# board_pa94.net
KiCad netlist of a schematic drawn in Altium Designer
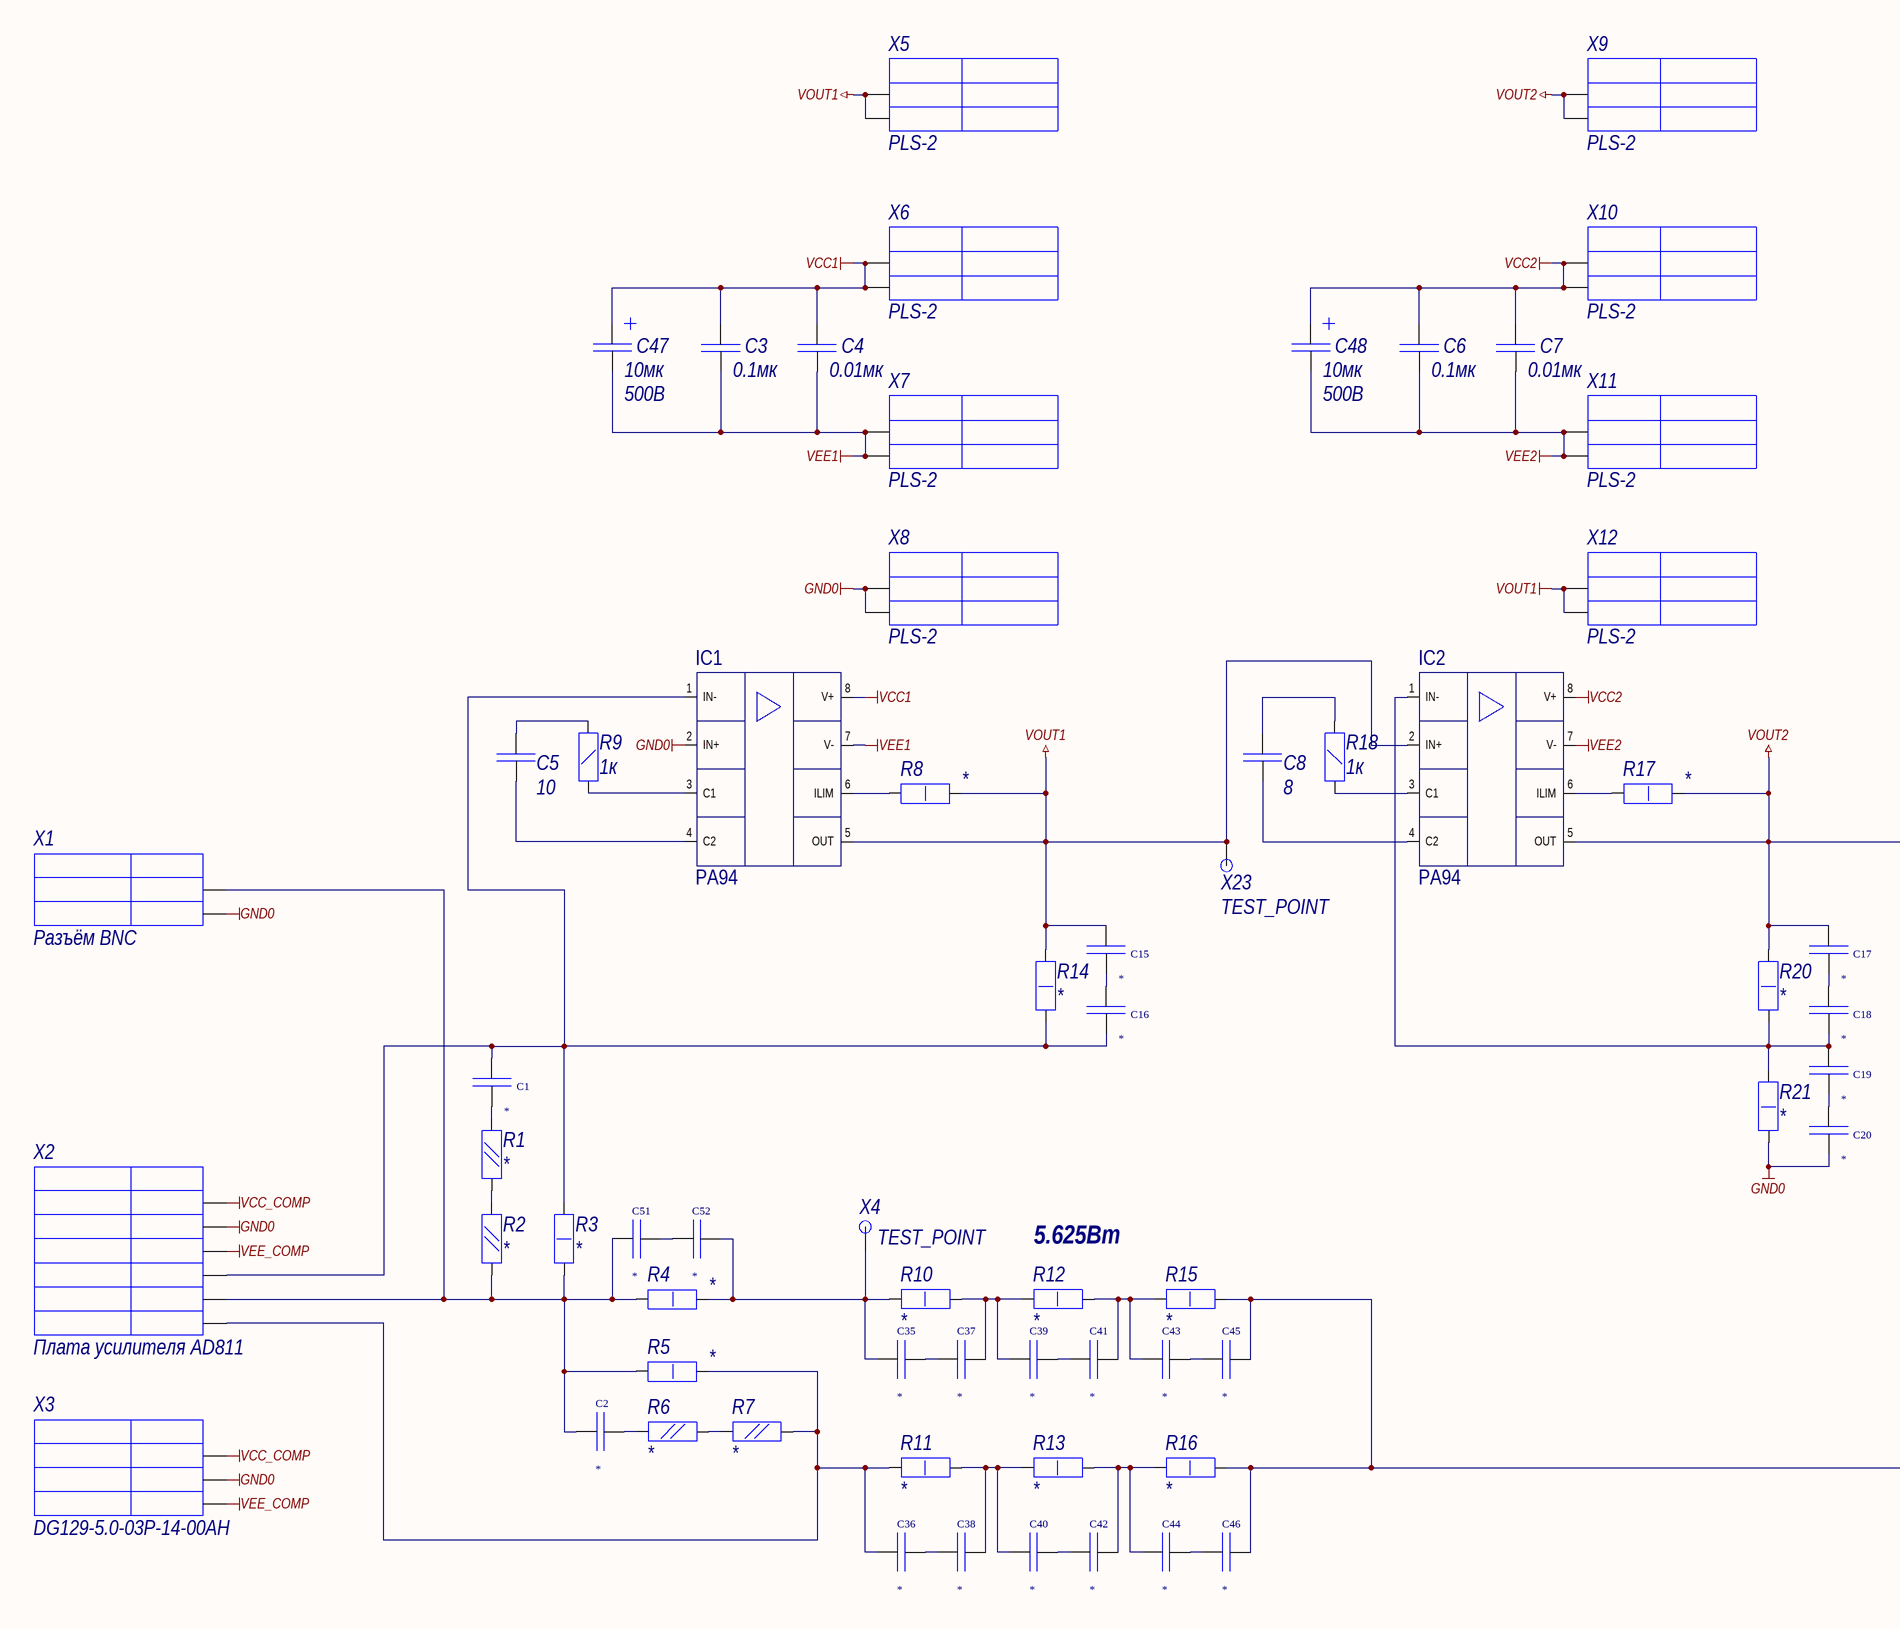
[diagram p0: board_pa94 (2).SchDoc, left]
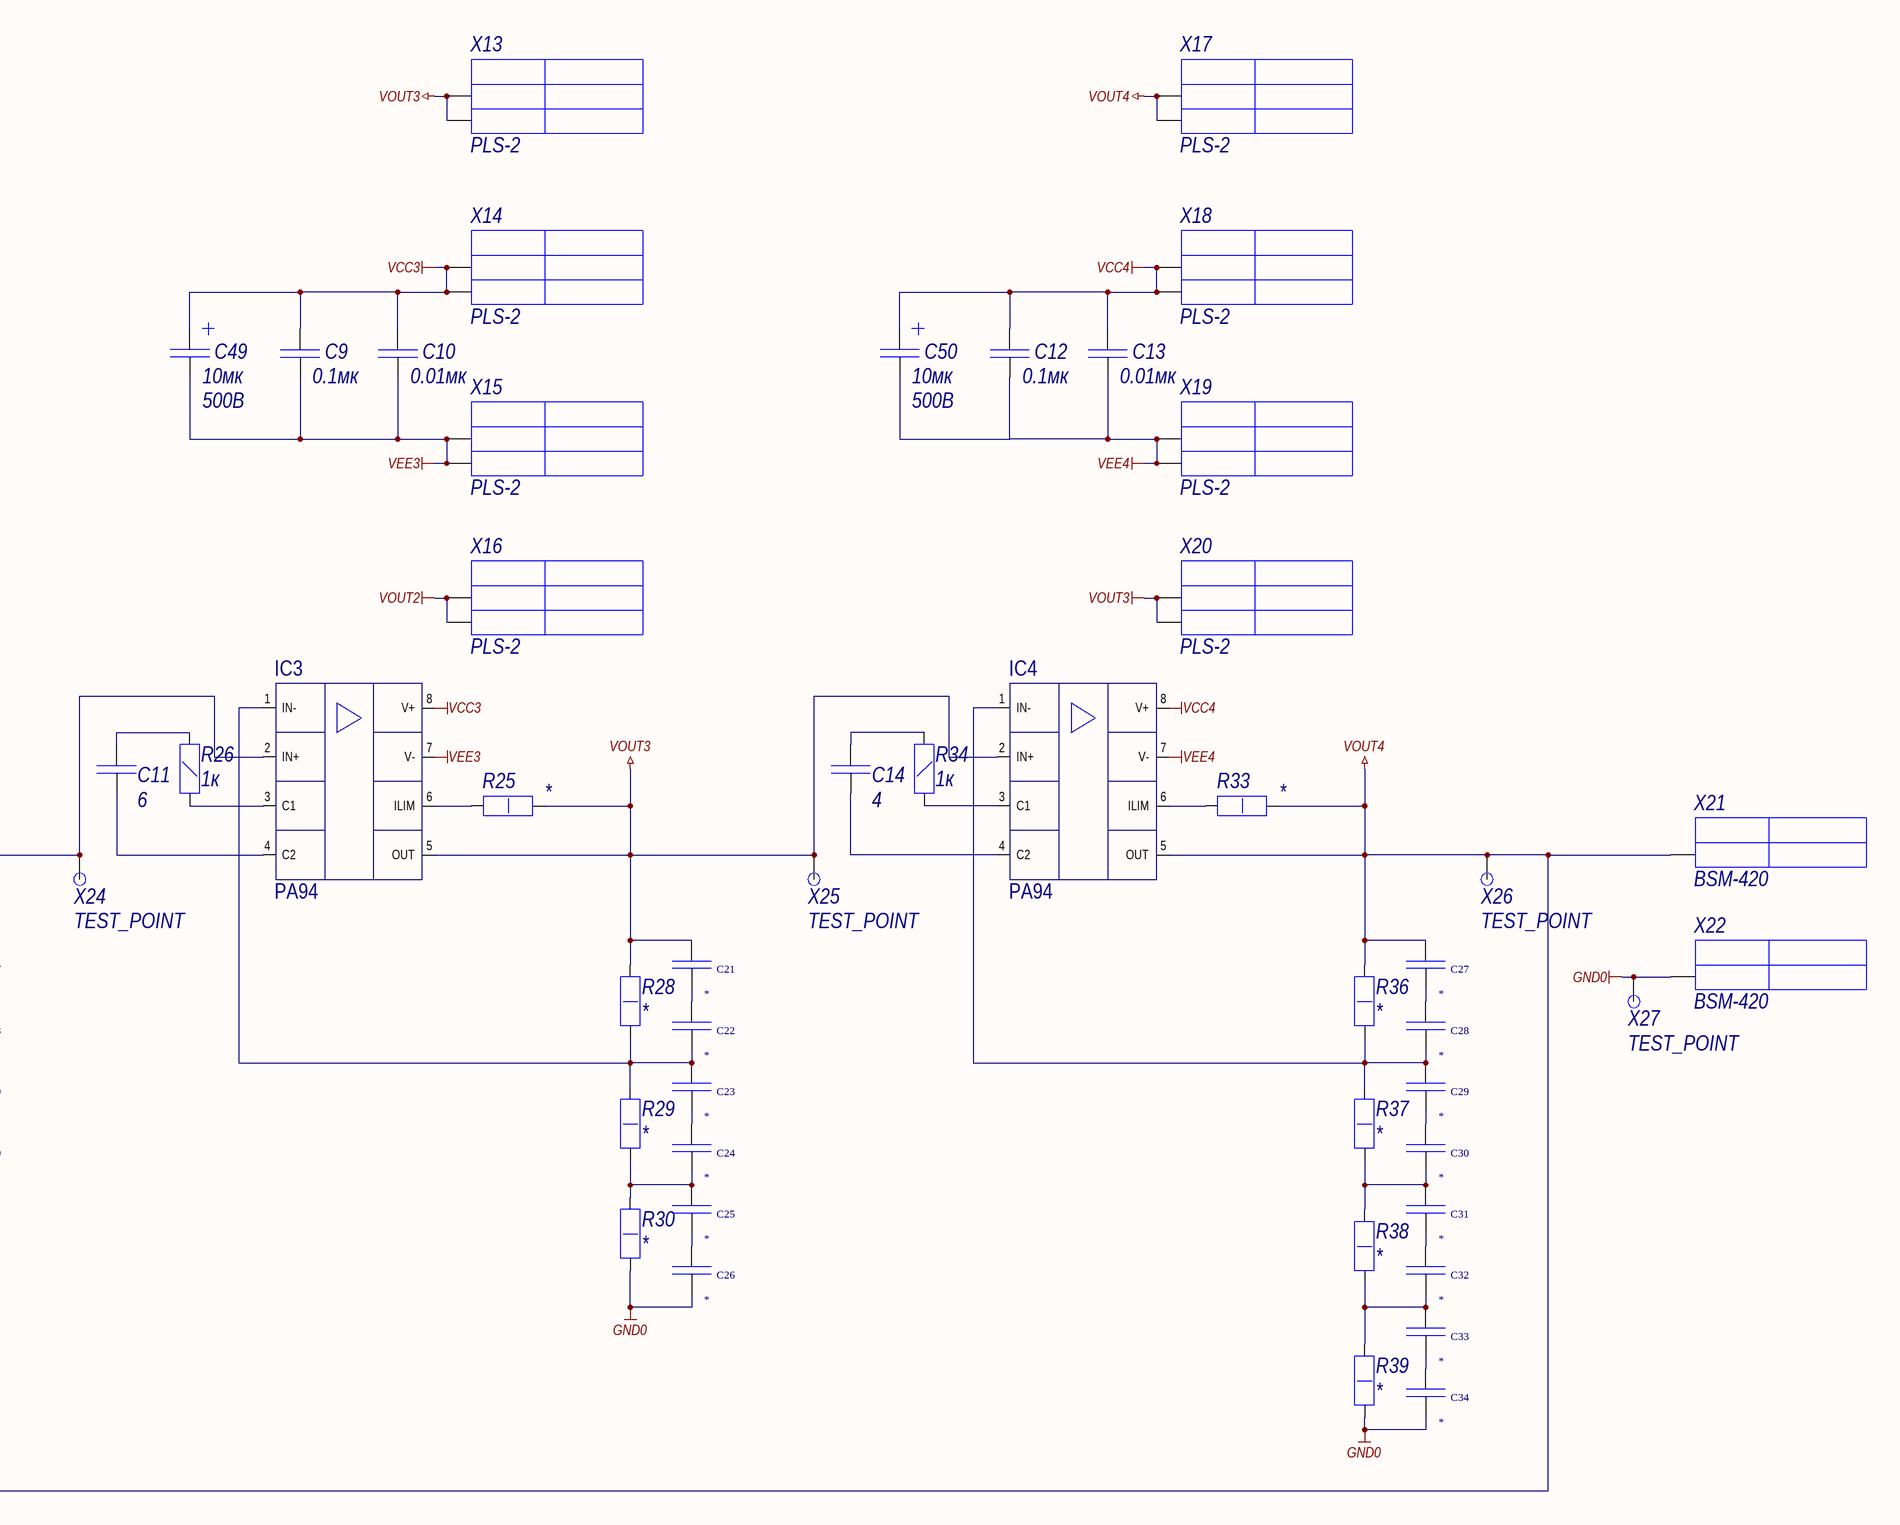
[diagram p1: board_pa94 (2).SchDoc, right]

(export (version "E")
  (design (tool "Eeschema 10.0.6"))
  (components
    (comp (ref "C1") (value "*") (footprint "C-0805") (libsource (lib "Capacitor") (part "C0805")))
    (comp (ref "C2") (value "*") (footprint "C-0805") (libsource (lib "Capacitor") (part "C0805")))
    (comp (ref "C3")
      (value "0.1мк")
      (footprint "C-1812")
      (fields (field (name "VOLTAGE") "630"))
      (libsource (lib "Capacitor") (part "C1812"))
    )
    (comp (ref "C4")
      (value "0.01мк")
      (footprint "C-1206")
      (fields (field (name "VOLTAGE") "630"))
      (libsource (lib "Capacitor") (part "C1206"))
    )
    (comp (ref "C5")
      (value "10")
      (footprint "C-1206")
      (fields (field (name "VOLTAGE") "630В"))
      (libsource (lib "Capacitor") (part "C1206"))
    )
    (comp (ref "C6")
      (value "0.1мк")
      (footprint "C-1812")
      (fields (field (name "VOLTAGE") "630"))
      (libsource (lib "Capacitor") (part "C1812"))
    )
    (comp (ref "C7")
      (value "0.01мк")
      (footprint "C-1206")
      (fields (field (name "VOLTAGE") "630"))
      (libsource (lib "Capacitor") (part "C1206"))
    )
    (comp (ref "C8")
      (value "8")
      (footprint "C-1206")
      (fields (field (name "VOLTAGE") "630В"))
      (libsource (lib "Capacitor") (part "C1206"))
    )
    (comp (ref "C9")
      (value "0.1мк")
      (footprint "C-1812")
      (fields (field (name "VOLTAGE") "630"))
      (libsource (lib "Capacitor") (part "C1812"))
    )
    (comp (ref "C10")
      (value "0.01мк")
      (footprint "C-1206")
      (fields (field (name "VOLTAGE") "630"))
      (libsource (lib "Capacitor") (part "C1206"))
    )
    (comp (ref "C11")
      (value "6")
      (footprint "C-1206")
      (fields (field (name "VOLTAGE") "630В"))
      (libsource (lib "Capacitor") (part "C1206"))
    )
    (comp (ref "C12")
      (value "0.1мк")
      (footprint "C-1812")
      (fields (field (name "VOLTAGE") "630"))
      (libsource (lib "Capacitor") (part "C1812"))
    )
    (comp (ref "C13")
      (value "0.01мк")
      (footprint "C-1206")
      (fields (field (name "VOLTAGE") "630"))
      (libsource (lib "Capacitor") (part "C1206"))
    )
    (comp (ref "C14")
      (value "4")
      (footprint "C-1206")
      (fields (field (name "VOLTAGE") "630В"))
      (libsource (lib "Capacitor") (part "C1206"))
    )
    (comp (ref "C15") (value "*") (footprint "C-0805") (libsource (lib "Capacitor") (part "C0805")))
    (comp (ref "C16") (value "*") (footprint "C-0805") (libsource (lib "Capacitor") (part "C0805")))
    (comp (ref "C17") (value "*") (footprint "C-0805") (libsource (lib "Capacitor") (part "C0805")))
    (comp (ref "C18") (value "*") (footprint "C-0805") (libsource (lib "Capacitor") (part "C0805")))
    (comp (ref "C19") (value "*") (footprint "C-0805") (libsource (lib "Capacitor") (part "C0805")))
    (comp (ref "C20") (value "*") (footprint "C-0805") (libsource (lib "Capacitor") (part "C0805")))
    (comp (ref "C21") (value "*") (footprint "C-0805") (libsource (lib "Capacitor") (part "C0805")))
    (comp (ref "C22") (value "*") (footprint "C-0805") (libsource (lib "Capacitor") (part "C0805")))
    (comp (ref "C23") (value "*") (footprint "C-0805") (libsource (lib "Capacitor") (part "C0805")))
    (comp (ref "C24") (value "*") (footprint "C-0805") (libsource (lib "Capacitor") (part "C0805")))
    (comp (ref "C25") (value "*") (footprint "C-0805") (libsource (lib "Capacitor") (part "C0805")))
    (comp (ref "C26") (value "*") (footprint "C-0805") (libsource (lib "Capacitor") (part "C0805")))
    (comp (ref "C27") (value "*") (footprint "C-0805") (libsource (lib "Capacitor") (part "C0805")))
    (comp (ref "C28") (value "*") (footprint "C-0805") (libsource (lib "Capacitor") (part "C0805")))
    (comp (ref "C29") (value "*") (footprint "C-0805") (libsource (lib "Capacitor") (part "C0805")))
    (comp (ref "C30") (value "*") (footprint "C-0805") (libsource (lib "Capacitor") (part "C0805")))
    (comp (ref "C31") (value "*") (footprint "C-0805") (libsource (lib "Capacitor") (part "C0805")))
    (comp (ref "C32") (value "*") (footprint "C-0805") (libsource (lib "Capacitor") (part "C0805")))
    (comp (ref "C33") (value "*") (footprint "C-0805") (libsource (lib "Capacitor") (part "C0805")))
    (comp (ref "C34") (value "*") (footprint "C-0805") (libsource (lib "Capacitor") (part "C0805")))
    (comp (ref "C35") (value "*") (footprint "C-0805") (libsource (lib "Capacitor") (part "C0805")))
    (comp (ref "C36") (value "*") (footprint "C-0805") (libsource (lib "Capacitor") (part "C0805")))
    (comp (ref "C37") (value "*") (footprint "C-0805") (libsource (lib "Capacitor") (part "C0805")))
    (comp (ref "C38") (value "*") (footprint "C-0805") (libsource (lib "Capacitor") (part "C0805")))
    (comp (ref "C39") (value "*") (footprint "C-0805") (libsource (lib "Capacitor") (part "C0805")))
    (comp (ref "C40") (value "*") (footprint "C-0805") (libsource (lib "Capacitor") (part "C0805")))
    (comp (ref "C41") (value "*") (footprint "C-0805") (libsource (lib "Capacitor") (part "C0805")))
    (comp (ref "C42") (value "*") (footprint "C-0805") (libsource (lib "Capacitor") (part "C0805")))
    (comp (ref "C43") (value "*") (footprint "C-0805") (libsource (lib "Capacitor") (part "C0805")))
    (comp (ref "C44") (value "*") (footprint "C-0805") (libsource (lib "Capacitor") (part "C0805")))
    (comp (ref "C45") (value "*") (footprint "C-0805") (libsource (lib "Capacitor") (part "C0805")))
    (comp (ref "C46") (value "*") (footprint "C-0805") (libsource (lib "Capacitor") (part "C0805")))
    (comp (ref "C47")
      (value "10мк")
      (footprint "CAP: D10C5H12.5")
      (description "Конденсатор электролитический")
      (fields (field (name "VOLTAGE") "500В"))
      (libsource (lib "Capacitor") (part "Aluminum electrolytic capacitor"))
    )
    (comp (ref "C48")
      (value "10мк")
      (footprint "CAP: D10C5H12.5")
      (description "Конденсатор электролитический")
      (fields (field (name "VOLTAGE") "500В"))
      (libsource (lib "Capacitor") (part "Aluminum electrolytic capacitor"))
    )
    (comp (ref "C49")
      (value "10мк")
      (footprint "CAP: D10C5H12.5")
      (description "Конденсатор электролитический")
      (fields (field (name "VOLTAGE") "500В"))
      (libsource (lib "Capacitor") (part "Aluminum electrolytic capacitor"))
    )
    (comp (ref "C50")
      (value "10мк")
      (footprint "CAP: D10C5H12.5")
      (description "Конденсатор электролитический")
      (fields (field (name "VOLTAGE") "500В"))
      (libsource (lib "Capacitor") (part "Aluminum electrolytic capacitor"))
    )
    (comp (ref "C51") (value "*") (footprint "C-0805") (libsource (lib "Capacitor") (part "C0805")))
    (comp (ref "C52") (value "*") (footprint "C-0805") (libsource (lib "Capacitor") (part "C0805")))
    (comp (ref "IC1")
      (value "PA94")
      (footprint "PCBComponent_1")
      (description "Power Amplifier 1 Circuit 8-SIP")
      (fields (field (name "MF") "Apex Microtechnology") (field (name "DIGI-KEY_PART_NUMBER") "598-1334-ND"))
      (libsource (lib "PA94") (part "PA94"))
    )
    (comp (ref "IC2")
      (value "PA94")
      (footprint "PCBComponent_1")
      (description "Power Amplifier 1 Circuit 8-SIP")
      (fields (field (name "MF") "Apex Microtechnology") (field (name "DIGI-KEY_PART_NUMBER") "598-1334-ND"))
      (libsource (lib "PA94") (part "PA94"))
    )
    (comp (ref "IC3")
      (value "PA94")
      (footprint "PCBComponent_1")
      (description "Power Amplifier 1 Circuit 8-SIP")
      (fields (field (name "MF") "Apex Microtechnology") (field (name "DIGI-KEY_PART_NUMBER") "598-1334-ND"))
      (libsource (lib "PA94") (part "PA94"))
    )
    (comp (ref "IC4")
      (value "PA94")
      (footprint "PCBComponent_1")
      (description "Power Amplifier 1 Circuit 8-SIP")
      (fields (field (name "MF") "Apex Microtechnology") (field (name "DIGI-KEY_PART_NUMBER") "598-1334-ND"))
      (libsource (lib "PA94") (part "PA94"))
    )
    (comp (ref "R1")
      (value "*")
      (footprint "R-0805")
      (description "Резистор SMD")
      (fields (field (name "TOLERANCE") "5%"))
      (libsource (lib "Resistor") (part "R0805"))
    )
    (comp (ref "R2")
      (value "*")
      (footprint "R-0805")
      (description "Резистор SMD")
      (fields (field (name "TOLERANCE") "5%"))
      (libsource (lib "Resistor") (part "R0805"))
    )
    (comp (ref "R3")
      (value "*")
      (footprint "R-2512")
      (description "Резистор SMD")
      (fields (field (name "TOLERANCE") "5%"))
      (libsource (lib "Resistor") (part "R2512"))
    )
    (comp (ref "R4")
      (value "*")
      (footprint "R-2512")
      (description "Резистор SMD")
      (fields (field (name "TOLERANCE") "5%"))
      (libsource (lib "Resistor") (part "R2512"))
    )
    (comp (ref "R5")
      (value "*")
      (footprint "R-2512")
      (description "Резистор SMD")
      (fields (field (name "TOLERANCE") "5%"))
      (libsource (lib "Resistor") (part "R2512"))
    )
    (comp (ref "R6")
      (value "*")
      (footprint "R-0805")
      (description "Резистор SMD")
      (fields (field (name "TOLERANCE") "5%"))
      (libsource (lib "Resistor") (part "R0805"))
    )
    (comp (ref "R7")
      (value "*")
      (footprint "R-0805")
      (description "Резистор SMD")
      (fields (field (name "TOLERANCE") "5%"))
      (libsource (lib "Resistor") (part "R0805"))
    )
    (comp (ref "R8")
      (value "*")
      (footprint "R-2512")
      (description "Резистор SMD")
      (fields (field (name "TOLERANCE") "5%"))
      (libsource (lib "Resistor") (part "R2512"))
    )
    (comp (ref "R9")
      (value "1к")
      (footprint "R-1206")
      (description "Резистор SMD")
      (fields (field (name "TOLERANCE") "5%"))
      (libsource (lib "Resistor") (part "R1206"))
    )
    (comp (ref "R10")
      (value "*")
      (footprint "R-2512")
      (description "Резистор SMD")
      (fields (field (name "TOLERANCE") "5%"))
      (libsource (lib "Resistor") (part "R2512"))
    )
    (comp (ref "R11")
      (value "*")
      (footprint "R-2512")
      (description "Резистор SMD")
      (fields (field (name "TOLERANCE") "5%"))
      (libsource (lib "Resistor") (part "R2512"))
    )
    (comp (ref "R12")
      (value "*")
      (footprint "R-2512")
      (description "Резистор SMD")
      (fields (field (name "TOLERANCE") "5%"))
      (libsource (lib "Resistor") (part "R2512"))
    )
    (comp (ref "R13")
      (value "*")
      (footprint "R-2512")
      (description "Резистор SMD")
      (fields (field (name "TOLERANCE") "5%"))
      (libsource (lib "Resistor") (part "R2512"))
    )
    (comp (ref "R14")
      (value "*")
      (footprint "R-2512")
      (description "Резистор SMD")
      (fields (field (name "TOLERANCE") "5%"))
      (libsource (lib "Resistor") (part "R2512"))
    )
    (comp (ref "R15")
      (value "*")
      (footprint "R-2512")
      (description "Резистор SMD")
      (fields (field (name "TOLERANCE") "5%"))
      (libsource (lib "Resistor") (part "R2512"))
    )
    (comp (ref "R16")
      (value "*")
      (footprint "R-2512")
      (description "Резистор SMD")
      (fields (field (name "TOLERANCE") "5%"))
      (libsource (lib "Resistor") (part "R2512"))
    )
    (comp (ref "R17")
      (value "*")
      (footprint "R-2512")
      (description "Резистор SMD")
      (fields (field (name "TOLERANCE") "5%"))
      (libsource (lib "Resistor") (part "R2512"))
    )
    (comp (ref "R18")
      (value "1к")
      (footprint "R-1206")
      (description "Резистор SMD")
      (fields (field (name "TOLERANCE") "5%"))
      (libsource (lib "Resistor") (part "R1206"))
    )
    (comp (ref "R20")
      (value "*")
      (footprint "R-2512")
      (description "Резистор SMD")
      (fields (field (name "TOLERANCE") "5%"))
      (libsource (lib "Resistor") (part "R2512"))
    )
    (comp (ref "R21")
      (value "*")
      (footprint "R-2512")
      (description "Резистор SMD")
      (fields (field (name "TOLERANCE") "5%"))
      (libsource (lib "Resistor") (part "R2512"))
    )
    (comp (ref "R25")
      (value "*")
      (footprint "R-2512")
      (description "Резистор SMD")
      (fields (field (name "TOLERANCE") "5%"))
      (libsource (lib "Resistor") (part "R2512"))
    )
    (comp (ref "R26")
      (value "1к")
      (footprint "R-1206")
      (description "Резистор SMD")
      (fields (field (name "TOLERANCE") "5%"))
      (libsource (lib "Resistor") (part "R1206"))
    )
    (comp (ref "R28")
      (value "*")
      (footprint "R-2512")
      (description "Резистор SMD")
      (fields (field (name "TOLERANCE") "5%"))
      (libsource (lib "Resistor") (part "R2512"))
    )
    (comp (ref "R29")
      (value "*")
      (footprint "R-2512")
      (description "Резистор SMD")
      (fields (field (name "TOLERANCE") "5%"))
      (libsource (lib "Resistor") (part "R2512"))
    )
    (comp (ref "R30")
      (value "*")
      (footprint "R-2512")
      (description "Резистор SMD")
      (fields (field (name "TOLERANCE") "5%"))
      (libsource (lib "Resistor") (part "R2512"))
    )
    (comp (ref "R33")
      (value "*")
      (footprint "R-2512")
      (description "Резистор SMD")
      (fields (field (name "TOLERANCE") "5%"))
      (libsource (lib "Resistor") (part "R2512"))
    )
    (comp (ref "R34")
      (value "1к")
      (footprint "R-1206")
      (description "Резистор SMD")
      (fields (field (name "TOLERANCE") "5%"))
      (libsource (lib "Resistor") (part "R1206"))
    )
    (comp (ref "R36")
      (value "*")
      (footprint "R-2512")
      (description "Резистор SMD")
      (fields (field (name "TOLERANCE") "5%"))
      (libsource (lib "Resistor") (part "R2512"))
    )
    (comp (ref "R37")
      (value "*")
      (footprint "R-2512")
      (description "Резистор SMD")
      (fields (field (name "TOLERANCE") "5%"))
      (libsource (lib "Resistor") (part "R2512"))
    )
    (comp (ref "R38")
      (value "*")
      (footprint "R-2512")
      (description "Резистор SMD")
      (fields (field (name "TOLERANCE") "5%"))
      (libsource (lib "Resistor") (part "R2512"))
    )
    (comp (ref "R39")
      (value "*")
      (footprint "R-2512")
      (description "Резистор SMD")
      (fields (field (name "TOLERANCE") "5%"))
      (libsource (lib "Resistor") (part "R2512"))
    )
    (comp (ref "X1")
      (value "Разъём BNC")
      (footprint "BNC")
      (description "Разъём")
      (fields (field (name "PARTNUMBER") "32K249-400L5"))
      (libsource (lib "CONNECTORS") (part "BNC"))
    )
    (comp (ref "X2")
      (value "Плата усилителя AD811")
      (footprint "BOARD_AD811")
      (libsource (lib "BOARDS") (part "BOARD_AD811"))
    )
    (comp (ref "X3")
      (value "DG129-5.0-03P-14-00AH")
      (footprint "DG129-5.0-03P-14-00AH")
      (description "Разъем винтовой")
      (libsource (lib "CONNECTORS") (part "DG129-5.0-03P-14-00AH"))
    )
    (comp (ref "X4")
      (value "TEST_POINT")
      (footprint "TEST_POINT")
      (description "Тестовый контакт")
      (libsource (lib "CONNECTORS") (part "TEST_POINT"))
    )
    (comp (ref "X5")
      (value "PLS-2")
      (footprint "PLS-2")
      (description "Разъём штыревой")
      (libsource (lib "CONNECTORS") (part "PLS-2"))
    )
    (comp (ref "X6")
      (value "PLS-2")
      (footprint "PLS-2")
      (description "Разъём штыревой")
      (libsource (lib "CONNECTORS") (part "PLS-2"))
    )
    (comp (ref "X7")
      (value "PLS-2")
      (footprint "PLS-2")
      (description "Разъём штыревой")
      (libsource (lib "CONNECTORS") (part "PLS-2"))
    )
    (comp (ref "X8")
      (value "PLS-2")
      (footprint "PLS-2")
      (description "Разъём штыревой")
      (libsource (lib "CONNECTORS") (part "PLS-2"))
    )
    (comp (ref "X9")
      (value "PLS-2")
      (footprint "PLS-2")
      (description "Разъём штыревой")
      (libsource (lib "CONNECTORS") (part "PLS-2"))
    )
    (comp (ref "X10")
      (value "PLS-2")
      (footprint "PLS-2")
      (description "Разъём штыревой")
      (libsource (lib "CONNECTORS") (part "PLS-2"))
    )
    (comp (ref "X11")
      (value "PLS-2")
      (footprint "PLS-2")
      (description "Разъём штыревой")
      (libsource (lib "CONNECTORS") (part "PLS-2"))
    )
    (comp (ref "X12")
      (value "PLS-2")
      (footprint "PLS-2")
      (description "Разъём штыревой")
      (libsource (lib "CONNECTORS") (part "PLS-2"))
    )
    (comp (ref "X13")
      (value "PLS-2")
      (footprint "PLS-2")
      (description "Разъём штыревой")
      (libsource (lib "CONNECTORS") (part "PLS-2"))
    )
    (comp (ref "X14")
      (value "PLS-2")
      (footprint "PLS-2")
      (description "Разъём штыревой")
      (libsource (lib "CONNECTORS") (part "PLS-2"))
    )
    (comp (ref "X15")
      (value "PLS-2")
      (footprint "PLS-2")
      (description "Разъём штыревой")
      (libsource (lib "CONNECTORS") (part "PLS-2"))
    )
    (comp (ref "X16")
      (value "PLS-2")
      (footprint "PLS-2")
      (description "Разъём штыревой")
      (libsource (lib "CONNECTORS") (part "PLS-2"))
    )
    (comp (ref "X17")
      (value "PLS-2")
      (footprint "PLS-2")
      (description "Разъём штыревой")
      (libsource (lib "CONNECTORS") (part "PLS-2"))
    )
    (comp (ref "X18")
      (value "PLS-2")
      (footprint "PLS-2")
      (description "Разъём штыревой")
      (libsource (lib "CONNECTORS") (part "PLS-2"))
    )
    (comp (ref "X19")
      (value "PLS-2")
      (footprint "PLS-2")
      (description "Разъём штыревой")
      (libsource (lib "CONNECTORS") (part "PLS-2"))
    )
    (comp (ref "X20")
      (value "PLS-2")
      (footprint "PLS-2")
      (description "Разъём штыревой")
      (libsource (lib "CONNECTORS") (part "PLS-2"))
    )
    (comp (ref "X21")
      (value "BSM-420")
      (footprint "BSM-420-R")
      (description "Разъём")
      (fields (field (name "PARTNUMBER") "32K249-400L5"))
      (libsource (lib "CONNECTORS") (part "BSM-420"))
    )
    (comp (ref "X22")
      (value "BSM-420")
      (footprint "BSM-420-B")
      (description "Разъём")
      (fields (field (name "PARTNUMBER") "32K249-400L5"))
      (libsource (lib "CONNECTORS") (part "BSM-420"))
    )
    (comp (ref "X23")
      (value "TEST_POINT")
      (footprint "TEST_POINT")
      (description "Тестовый контакт")
      (libsource (lib "CONNECTORS") (part "TEST_POINT"))
    )
    (comp (ref "X24")
      (value "TEST_POINT")
      (footprint "TEST_POINT")
      (description "Тестовый контакт")
      (libsource (lib "CONNECTORS") (part "TEST_POINT"))
    )
    (comp (ref "X25")
      (value "TEST_POINT")
      (footprint "TEST_POINT")
      (description "Тестовый контакт")
      (libsource (lib "CONNECTORS") (part "TEST_POINT"))
    )
    (comp (ref "X26")
      (value "TEST_POINT")
      (footprint "TEST_POINT")
      (description "Тестовый контакт")
      (libsource (lib "CONNECTORS") (part "TEST_POINT"))
    )
    (comp (ref "X27")
      (value "TEST_POINT")
      (footprint "TEST_POINT")
      (description "Тестовый контакт")
      (libsource (lib "CONNECTORS") (part "TEST_POINT"))
    )
  )
  (nets
    (net (code "1") (name "GND0") (class "Default")
      (node (ref "C20") (pin "2") (pintype "passive"))
      (node (ref "C26") (pin "2") (pintype "passive"))
      (node (ref "C34") (pin "2") (pintype "passive"))
      (node (ref "IC1") (pin "2") (pinfunction "IN+_2") (pintype "passive"))
      (node (ref "R21") (pin "1") (pintype "passive"))
      (node (ref "R30") (pin "1") (pintype "passive"))
      (node (ref "R39") (pin "1") (pintype "passive"))
      (node (ref "X1") (pin "2") (pintype "passive"))
      (node (ref "X2") (pin "2") (pintype "passive"))
      (node (ref "X22") (pin "1") (pintype "passive"))
      (node (ref "X27") (pin "1") (pinfunction "1_1") (pintype "passive"))
      (node (ref "X3") (pin "2") (pintype "passive"))
      (node (ref "X8") (pin "1") (pintype "passive"))
      (node (ref "X8") (pin "2") (pintype "passive"))
    )
    (net (code "2") (name "Net-(C1-Pad2)") (class "Default")
      (node (ref "C1") (pin "2") (pintype "passive"))
      (node (ref "R1") (pin "2") (pintype "passive"))
    )
    (net (code "3") (name "Net-(C2-Pad1)") (class "Default")
      (node (ref "C2") (pin "1") (pintype "passive"))
      (node (ref "C51") (pin "1") (pintype "passive"))
      (node (ref "R2") (pin "1") (pintype "passive"))
      (node (ref "R3") (pin "1") (pintype "passive"))
      (node (ref "R4") (pin "1") (pintype "passive"))
      (node (ref "R5") (pin "1") (pintype "passive"))
      (node (ref "X1") (pin "1") (pintype "passive"))
      (node (ref "X2") (pin "5") (pintype "passive"))
    )
    (net (code "4") (name "Net-(C2-Pad2)") (class "Default")
      (node (ref "C2") (pin "2") (pintype "passive"))
      (node (ref "R6") (pin "2") (pintype "passive"))
    )
    (net (code "5") (name "Net-(C5-Pad1)") (class "Default")
      (node (ref "C5") (pin "1") (pintype "passive"))
      (node (ref "R9") (pin "1") (pintype "passive"))
    )
    (net (code "6") (name "Net-(C8-Pad2)") (class "Default")
      (node (ref "C8") (pin "2") (pintype "passive"))
      (node (ref "R18") (pin "2") (pintype "passive"))
    )
    (net (code "7") (name "Net-(C11-Pad2)") (class "Default")
      (node (ref "C11") (pin "2") (pintype "passive"))
      (node (ref "R26") (pin "2") (pintype "passive"))
    )
    (net (code "8") (name "Net-(C14-Pad1)") (class "Default")
      (node (ref "C14") (pin "1") (pintype "passive"))
      (node (ref "R34") (pin "1") (pintype "passive"))
    )
    (net (code "9") (name "Net-(C15-Pad2)") (class "Default")
      (node (ref "C15") (pin "2") (pintype "passive"))
      (node (ref "C16") (pin "1") (pintype "passive"))
    )
    (net (code "10") (name "Net-(C17-Pad2)") (class "Default")
      (node (ref "C17") (pin "2") (pintype "passive"))
      (node (ref "C18") (pin "1") (pintype "passive"))
    )
    (net (code "11") (name "Net-(C19-Pad2)") (class "Default")
      (node (ref "C19") (pin "2") (pintype "passive"))
      (node (ref "C20") (pin "1") (pintype "passive"))
    )
    (net (code "12") (name "Net-(C21-Pad2)") (class "Default")
      (node (ref "C21") (pin "2") (pintype "passive"))
      (node (ref "C22") (pin "1") (pintype "passive"))
    )
    (net (code "13") (name "Net-(C23-Pad2)") (class "Default")
      (node (ref "C23") (pin "2") (pintype "passive"))
      (node (ref "C24") (pin "1") (pintype "passive"))
    )
    (net (code "14") (name "Net-(C24-Pad2)") (class "Default")
      (node (ref "C24") (pin "2") (pintype "passive"))
      (node (ref "C25") (pin "1") (pintype "passive"))
      (node (ref "R29") (pin "1") (pintype "passive"))
      (node (ref "R30") (pin "2") (pintype "passive"))
    )
    (net (code "15") (name "Net-(C25-Pad2)") (class "Default")
      (node (ref "C25") (pin "2") (pintype "passive"))
      (node (ref "C26") (pin "1") (pintype "passive"))
    )
    (net (code "16") (name "Net-(C27-Pad2)") (class "Default")
      (node (ref "C27") (pin "2") (pintype "passive"))
      (node (ref "C28") (pin "1") (pintype "passive"))
    )
    (net (code "17") (name "Net-(C29-Pad2)") (class "Default")
      (node (ref "C29") (pin "2") (pintype "passive"))
      (node (ref "C30") (pin "1") (pintype "passive"))
    )
    (net (code "18") (name "Net-(C30-Pad2)") (class "Default")
      (node (ref "C30") (pin "2") (pintype "passive"))
      (node (ref "C31") (pin "1") (pintype "passive"))
      (node (ref "R37") (pin "1") (pintype "passive"))
      (node (ref "R38") (pin "2") (pintype "passive"))
    )
    (net (code "19") (name "Net-(C31-Pad2)") (class "Default")
      (node (ref "C31") (pin "2") (pintype "passive"))
      (node (ref "C32") (pin "1") (pintype "passive"))
    )
    (net (code "20") (name "Net-(C32-Pad2)") (class "Default")
      (node (ref "C32") (pin "2") (pintype "passive"))
      (node (ref "C33") (pin "1") (pintype "passive"))
      (node (ref "R38") (pin "1") (pintype "passive"))
      (node (ref "R39") (pin "2") (pintype "passive"))
    )
    (net (code "21") (name "Net-(C33-Pad2)") (class "Default")
      (node (ref "C33") (pin "2") (pintype "passive"))
      (node (ref "C34") (pin "1") (pintype "passive"))
    )
    (net (code "22") (name "Net-(C35-Pad1)") (class "Default")
      (node (ref "C35") (pin "1") (pintype "passive"))
      (node (ref "C37") (pin "2") (pintype "passive"))
    )
    (net (code "23") (name "Net-(C35-Pad2)") (class "Default")
      (node (ref "C35") (pin "2") (pintype "passive"))
      (node (ref "C52") (pin "2") (pintype "passive"))
      (node (ref "R10") (pin "2") (pintype "passive"))
      (node (ref "R4") (pin "2") (pintype "passive"))
      (node (ref "X4") (pin "1") (pinfunction "1_1") (pintype "passive"))
    )
    (net (code "24") (name "Net-(C36-Pad1)") (class "Default")
      (node (ref "C36") (pin "1") (pintype "passive"))
      (node (ref "C38") (pin "2") (pintype "passive"))
    )
    (net (code "25") (name "Net-(C36-Pad2)") (class "Default")
      (node (ref "C36") (pin "2") (pintype "passive"))
      (node (ref "R11") (pin "2") (pintype "passive"))
      (node (ref "R5") (pin "2") (pintype "passive"))
      (node (ref "R7") (pin "1") (pintype "passive"))
      (node (ref "X2") (pin "6") (pintype "passive"))
    )
    (net (code "26") (name "Net-(C37-Pad1)") (class "Default")
      (node (ref "C37") (pin "1") (pintype "passive"))
      (node (ref "C39") (pin "2") (pintype "passive"))
      (node (ref "R10") (pin "1") (pintype "passive"))
      (node (ref "R12") (pin "2") (pintype "passive"))
    )
    (net (code "27") (name "Net-(C38-Pad1)") (class "Default")
      (node (ref "C38") (pin "1") (pintype "passive"))
      (node (ref "C40") (pin "2") (pintype "passive"))
      (node (ref "R11") (pin "1") (pintype "passive"))
      (node (ref "R13") (pin "2") (pintype "passive"))
    )
    (net (code "28") (name "Net-(C39-Pad1)") (class "Default")
      (node (ref "C39") (pin "1") (pintype "passive"))
      (node (ref "C41") (pin "2") (pintype "passive"))
    )
    (net (code "29") (name "Net-(C40-Pad1)") (class "Default")
      (node (ref "C40") (pin "1") (pintype "passive"))
      (node (ref "C42") (pin "2") (pintype "passive"))
    )
    (net (code "30") (name "Net-(C41-Pad1)") (class "Default")
      (node (ref "C41") (pin "1") (pintype "passive"))
      (node (ref "C43") (pin "2") (pintype "passive"))
      (node (ref "R12") (pin "1") (pintype "passive"))
      (node (ref "R15") (pin "2") (pintype "passive"))
    )
    (net (code "31") (name "Net-(C42-Pad1)") (class "Default")
      (node (ref "C42") (pin "1") (pintype "passive"))
      (node (ref "C44") (pin "2") (pintype "passive"))
      (node (ref "R13") (pin "1") (pintype "passive"))
      (node (ref "R16") (pin "2") (pintype "passive"))
    )
    (net (code "32") (name "Net-(C43-Pad1)") (class "Default")
      (node (ref "C43") (pin "1") (pintype "passive"))
      (node (ref "C45") (pin "2") (pintype "passive"))
    )
    (net (code "33") (name "Net-(C44-Pad1)") (class "Default")
      (node (ref "C44") (pin "1") (pintype "passive"))
      (node (ref "C46") (pin "2") (pintype "passive"))
    )
    (net (code "34") (name "Net-(C51-Pad2)") (class "Default")
      (node (ref "C51") (pin "2") (pintype "passive"))
      (node (ref "C52") (pin "1") (pintype "passive"))
    )
    (net (code "35") (name "Net-(IC1-C1)") (class "Default")
      (node (ref "IC1") (pin "3") (pinfunction "C1_3") (pintype "passive"))
      (node (ref "R9") (pin "2") (pintype "passive"))
    )
    (net (code "36") (name "Net-(IC1-C2)") (class "Default")
      (node (ref "C5") (pin "2") (pintype "passive"))
      (node (ref "IC1") (pin "4") (pinfunction "C2_4") (pintype "passive"))
    )
    (net (code "37") (name "Net-(IC1-ILIM)") (class "Default")
      (node (ref "IC1") (pin "6") (pinfunction "ILIM_6") (pintype "passive"))
      (node (ref "R8") (pin "1") (pintype "passive"))
    )
    (net (code "38") (name "Net-(IC1-IN-)") (class "Default")
      (node (ref "C1") (pin "1") (pintype "passive"))
      (node (ref "C16") (pin "2") (pintype "passive"))
      (node (ref "IC1") (pin "1") (pinfunction "IN-_1") (pintype "passive"))
      (node (ref "R14") (pin "1") (pintype "passive"))
      (node (ref "R3") (pin "2") (pintype "passive"))
      (node (ref "X2") (pin "4") (pintype "passive"))
    )
    (net (code "39") (name "Net-(IC2-C1)") (class "Default")
      (node (ref "IC2") (pin "3") (pinfunction "C1_3") (pintype "passive"))
      (node (ref "R18") (pin "1") (pintype "passive"))
    )
    (net (code "40") (name "Net-(IC2-C2)") (class "Default")
      (node (ref "C8") (pin "1") (pintype "passive"))
      (node (ref "IC2") (pin "4") (pinfunction "C2_4") (pintype "passive"))
    )
    (net (code "41") (name "Net-(IC2-ILIM)") (class "Default")
      (node (ref "IC2") (pin "6") (pinfunction "ILIM_6") (pintype "passive"))
      (node (ref "R17") (pin "1") (pintype "passive"))
    )
    (net (code "42") (name "Net-(IC2-IN-)") (class "Default")
      (node (ref "C18") (pin "2") (pintype "passive"))
      (node (ref "C19") (pin "1") (pintype "passive"))
      (node (ref "IC2") (pin "1") (pinfunction "IN-_1") (pintype "passive"))
      (node (ref "R20") (pin "1") (pintype "passive"))
      (node (ref "R21") (pin "2") (pintype "passive"))
    )
    (net (code "43") (name "Net-(IC3-C1)") (class "Default")
      (node (ref "IC3") (pin "3") (pinfunction "C1_3") (pintype "passive"))
      (node (ref "R26") (pin "1") (pintype "passive"))
    )
    (net (code "44") (name "Net-(IC3-C2)") (class "Default")
      (node (ref "C11") (pin "1") (pintype "passive"))
      (node (ref "IC3") (pin "4") (pinfunction "C2_4") (pintype "passive"))
    )
    (net (code "45") (name "Net-(IC3-ILIM)") (class "Default")
      (node (ref "IC3") (pin "6") (pinfunction "ILIM_6") (pintype "passive"))
      (node (ref "R25") (pin "1") (pintype "passive"))
    )
    (net (code "46") (name "Net-(IC3-IN-)") (class "Default")
      (node (ref "C22") (pin "2") (pintype "passive"))
      (node (ref "C23") (pin "1") (pintype "passive"))
      (node (ref "IC3") (pin "1") (pinfunction "IN-_1") (pintype "passive"))
      (node (ref "R28") (pin "1") (pintype "passive"))
      (node (ref "R29") (pin "2") (pintype "passive"))
    )
    (net (code "47") (name "Net-(IC4-C1)") (class "Default")
      (node (ref "IC4") (pin "3") (pinfunction "C1_3") (pintype "passive"))
      (node (ref "R34") (pin "2") (pintype "passive"))
    )
    (net (code "48") (name "Net-(IC4-C2)") (class "Default")
      (node (ref "C14") (pin "2") (pintype "passive"))
      (node (ref "IC4") (pin "4") (pinfunction "C2_4") (pintype "passive"))
    )
    (net (code "49") (name "Net-(IC4-ILIM)") (class "Default")
      (node (ref "IC4") (pin "6") (pinfunction "ILIM_6") (pintype "passive"))
      (node (ref "R33") (pin "1") (pintype "passive"))
    )
    (net (code "50") (name "Net-(IC4-IN-)") (class "Default")
      (node (ref "C28") (pin "2") (pintype "passive"))
      (node (ref "C29") (pin "1") (pintype "passive"))
      (node (ref "IC4") (pin "1") (pinfunction "IN-_1") (pintype "passive"))
      (node (ref "R36") (pin "1") (pintype "passive"))
      (node (ref "R37") (pin "2") (pintype "passive"))
    )
    (net (code "51") (name "Net-(R1-Pad1)") (class "Default")
      (node (ref "R1") (pin "1") (pintype "passive"))
      (node (ref "R2") (pin "2") (pintype "passive"))
    )
    (net (code "52") (name "Net-(R6-Pad1)") (class "Default")
      (node (ref "R6") (pin "1") (pintype "passive"))
      (node (ref "R7") (pin "2") (pintype "passive"))
    )
    (net (code "53") (name "VCC1") (class "Default")
      (node (ref "C3") (pin "2") (pintype "passive"))
      (node (ref "C4") (pin "2") (pintype "passive"))
      (node (ref "C47") (pin "1") (pintype "passive"))
      (node (ref "IC1") (pin "8") (pinfunction "V+_8") (pintype "passive"))
      (node (ref "X6") (pin "1") (pintype "passive"))
      (node (ref "X6") (pin "2") (pintype "passive"))
    )
    (net (code "54") (name "VCC2") (class "Default")
      (node (ref "C48") (pin "1") (pintype "passive"))
      (node (ref "C6") (pin "2") (pintype "passive"))
      (node (ref "C7") (pin "2") (pintype "passive"))
      (node (ref "IC2") (pin "8") (pinfunction "V+_8") (pintype "passive"))
      (node (ref "X10") (pin "1") (pintype "passive"))
      (node (ref "X10") (pin "2") (pintype "passive"))
    )
    (net (code "55") (name "VCC3") (class "Default")
      (node (ref "C10") (pin "2") (pintype "passive"))
      (node (ref "C49") (pin "1") (pintype "passive"))
      (node (ref "C9") (pin "2") (pintype "passive"))
      (node (ref "IC3") (pin "8") (pinfunction "V+_8") (pintype "passive"))
      (node (ref "X14") (pin "1") (pintype "passive"))
      (node (ref "X14") (pin "2") (pintype "passive"))
    )
    (net (code "56") (name "VCC4") (class "Default")
      (node (ref "C12") (pin "2") (pintype "passive"))
      (node (ref "C13") (pin "2") (pintype "passive"))
      (node (ref "C50") (pin "1") (pintype "passive"))
      (node (ref "IC4") (pin "8") (pinfunction "V+_8") (pintype "passive"))
      (node (ref "X18") (pin "1") (pintype "passive"))
      (node (ref "X18") (pin "2") (pintype "passive"))
    )
    (net (code "57") (name "VCC_COMP") (class "Default")
      (node (ref "X2") (pin "1") (pintype "passive"))
      (node (ref "X3") (pin "1") (pintype "passive"))
    )
    (net (code "58") (name "VEE1") (class "Default")
      (node (ref "C3") (pin "1") (pintype "passive"))
      (node (ref "C4") (pin "1") (pintype "passive"))
      (node (ref "C47") (pin "2") (pintype "passive"))
      (node (ref "IC1") (pin "7") (pinfunction "V-_7") (pintype "passive"))
      (node (ref "X7") (pin "1") (pintype "passive"))
      (node (ref "X7") (pin "2") (pintype "passive"))
    )
    (net (code "59") (name "VEE2") (class "Default")
      (node (ref "C48") (pin "2") (pintype "passive"))
      (node (ref "C6") (pin "1") (pintype "passive"))
      (node (ref "C7") (pin "1") (pintype "passive"))
      (node (ref "IC2") (pin "7") (pinfunction "V-_7") (pintype "passive"))
      (node (ref "X11") (pin "1") (pintype "passive"))
      (node (ref "X11") (pin "2") (pintype "passive"))
    )
    (net (code "60") (name "VEE3") (class "Default")
      (node (ref "C10") (pin "1") (pintype "passive"))
      (node (ref "C49") (pin "2") (pintype "passive"))
      (node (ref "C9") (pin "1") (pintype "passive"))
      (node (ref "IC3") (pin "7") (pinfunction "V-_7") (pintype "passive"))
      (node (ref "X15") (pin "1") (pintype "passive"))
      (node (ref "X15") (pin "2") (pintype "passive"))
    )
    (net (code "61") (name "VEE4") (class "Default")
      (node (ref "C12") (pin "1") (pintype "passive"))
      (node (ref "C13") (pin "1") (pintype "passive"))
      (node (ref "C50") (pin "2") (pintype "passive"))
      (node (ref "IC4") (pin "7") (pinfunction "V-_7") (pintype "passive"))
      (node (ref "X19") (pin "1") (pintype "passive"))
      (node (ref "X19") (pin "2") (pintype "passive"))
    )
    (net (code "62") (name "VEE_COMP") (class "Default")
      (node (ref "X2") (pin "3") (pintype "passive"))
      (node (ref "X3") (pin "3") (pintype "passive"))
    )
    (net (code "63") (name "VOUT1") (class "Default")
      (node (ref "C15") (pin "1") (pintype "passive"))
      (node (ref "IC1") (pin "5") (pinfunction "OUT_5") (pintype "passive"))
      (node (ref "IC2") (pin "2") (pinfunction "IN+_2") (pintype "passive"))
      (node (ref "R14") (pin "2") (pintype "passive"))
      (node (ref "R8") (pin "2") (pintype "passive"))
      (node (ref "X12") (pin "1") (pintype "passive"))
      (node (ref "X12") (pin "2") (pintype "passive"))
      (node (ref "X23") (pin "1") (pinfunction "1_1") (pintype "passive"))
      (node (ref "X5") (pin "1") (pintype "passive"))
      (node (ref "X5") (pin "2") (pintype "passive"))
    )
    (net (code "64") (name "VOUT2") (class "Default")
      (node (ref "C17") (pin "1") (pintype "passive"))
      (node (ref "IC2") (pin "5") (pinfunction "OUT_5") (pintype "passive"))
      (node (ref "IC3") (pin "2") (pinfunction "IN+_2") (pintype "passive"))
      (node (ref "R17") (pin "2") (pintype "passive"))
      (node (ref "R20") (pin "2") (pintype "passive"))
      (node (ref "X16") (pin "1") (pintype "passive"))
      (node (ref "X16") (pin "2") (pintype "passive"))
      (node (ref "X24") (pin "1") (pinfunction "1_1") (pintype "passive"))
      (node (ref "X9") (pin "1") (pintype "passive"))
      (node (ref "X9") (pin "2") (pintype "passive"))
    )
    (net (code "65") (name "VOUT3") (class "Default")
      (node (ref "C21") (pin "1") (pintype "passive"))
      (node (ref "IC3") (pin "5") (pinfunction "OUT_5") (pintype "passive"))
      (node (ref "IC4") (pin "2") (pinfunction "IN+_2") (pintype "passive"))
      (node (ref "R25") (pin "2") (pintype "passive"))
      (node (ref "R28") (pin "2") (pintype "passive"))
      (node (ref "X13") (pin "1") (pintype "passive"))
      (node (ref "X13") (pin "2") (pintype "passive"))
      (node (ref "X20") (pin "1") (pintype "passive"))
      (node (ref "X20") (pin "2") (pintype "passive"))
      (node (ref "X25") (pin "1") (pinfunction "1_1") (pintype "passive"))
    )
    (net (code "66") (name "VOUT4") (class "Default")
      (node (ref "C27") (pin "1") (pintype "passive"))
      (node (ref "C45") (pin "1") (pintype "passive"))
      (node (ref "C46") (pin "1") (pintype "passive"))
      (node (ref "IC4") (pin "5") (pinfunction "OUT_5") (pintype "passive"))
      (node (ref "R15") (pin "1") (pintype "passive"))
      (node (ref "R16") (pin "1") (pintype "passive"))
      (node (ref "R33") (pin "2") (pintype "passive"))
      (node (ref "R36") (pin "2") (pintype "passive"))
      (node (ref "X17") (pin "1") (pintype "passive"))
      (node (ref "X17") (pin "2") (pintype "passive"))
      (node (ref "X21") (pin "1") (pintype "passive"))
      (node (ref "X26") (pin "1") (pinfunction "1_1") (pintype "passive"))
    )
  )
)
